# kugarem_nosilk_fix.net
KiCad netlist of a schematic drawn in EAGLE
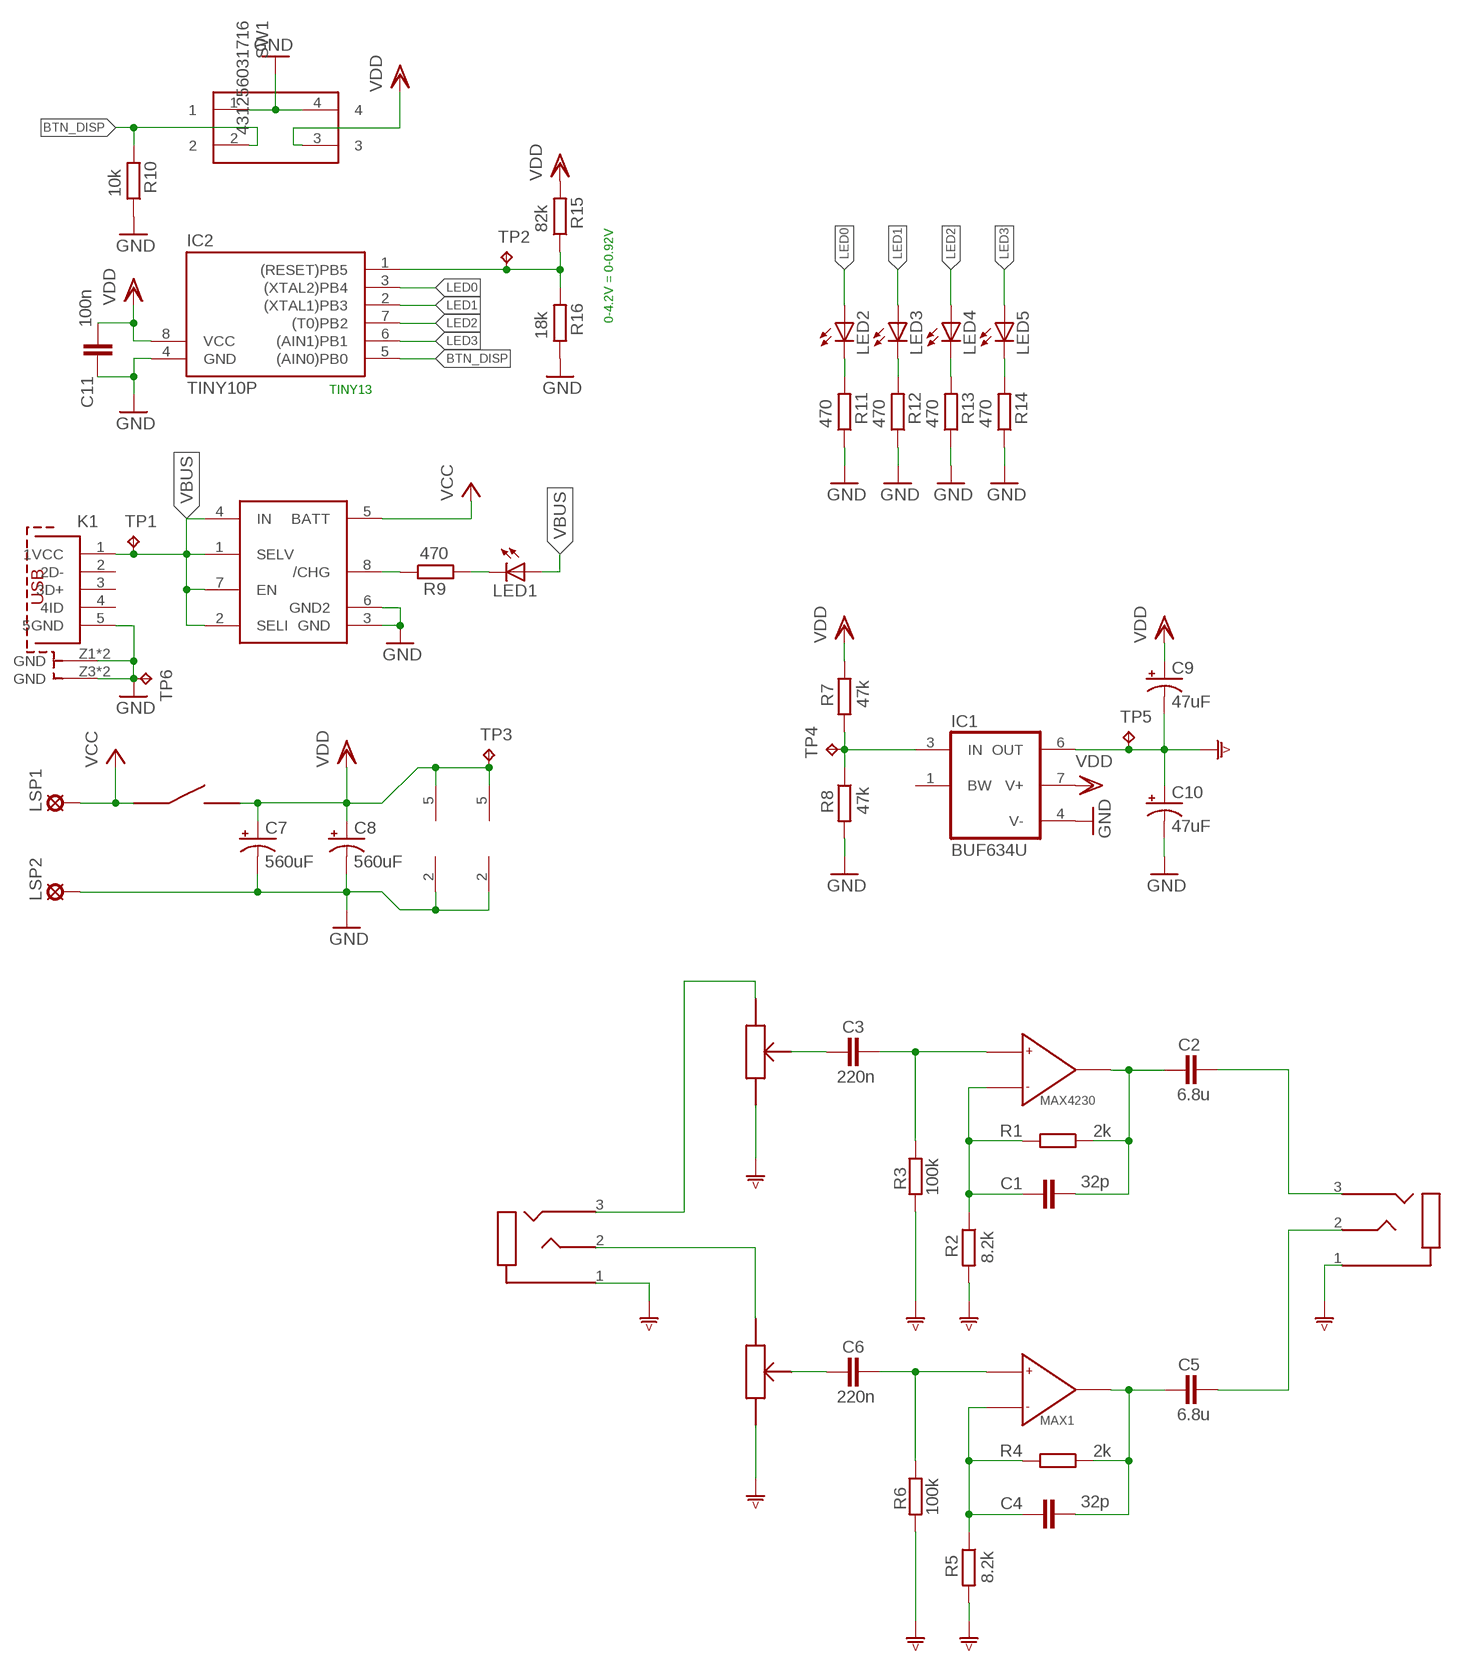
[diagram p0: schematic, sheet 1]

(export (version "E")
  (design (tool "Eeschema 10.0.6"))
  (components
    (comp (ref "C1")
      (value "32p")
      (footprint "eagle-import:C1206")
      (libsource (lib "eagle-import") (part "C-EUC1206"))
    )
    (comp (ref "C2")
      (value "6.8u")
      (footprint "eagle-import:C1206")
      (libsource (lib "eagle-import") (part "C-EUC1206"))
    )
    (comp (ref "C3")
      (value "220n")
      (footprint "eagle-import:C1206")
      (libsource (lib "eagle-import") (part "C-EUC1206"))
    )
    (comp (ref "C4")
      (value "32p")
      (footprint "eagle-import:C1206")
      (libsource (lib "eagle-import") (part "C-EUC1206"))
    )
    (comp (ref "C5")
      (value "6.8u")
      (footprint "eagle-import:C1206")
      (libsource (lib "eagle-import") (part "C-EUC1206"))
    )
    (comp (ref "C6")
      (value "220n")
      (footprint "eagle-import:C1206")
      (libsource (lib "eagle-import") (part "C-EUC1206"))
    )
    (comp (ref "C7")
      (value "560uF")
      (footprint "eagle-import:PANASONIC_G")
      (libsource (lib "eagle-import") (part "560UF-PANASONIC_G-25V-20%"))
    )
    (comp (ref "C8")
      (value "560uF")
      (footprint "eagle-import:PANASONIC_G")
      (libsource (lib "eagle-import") (part "560UF-PANASONIC_G-25V-20%"))
    )
    (comp (ref "C9")
      (value "47uF")
      (footprint "eagle-import:PANASONIC_D")
      (libsource (lib "eagle-import") (part "47UF-POLAR-PANASONIC_D-35V-20%"))
    )
    (comp (ref "C10")
      (value "47uF")
      (footprint "eagle-import:PANASONIC_D")
      (libsource (lib "eagle-import") (part "47UF-POLAR-PANASONIC_D-35V-20%"))
    )
    (comp (ref "C11")
      (value "100n")
      (footprint "eagle-import:C1206")
      (libsource (lib "eagle-import") (part "C-EUC1206"))
    )
    (comp (ref "IC1")
      (value "BUF634U")
      (footprint "eagle-import:SO08")
      (fields (field (name "MF") "TEXAS INSTRUMENTS"))
      (libsource (lib "eagle-import") (part "BUF634U"))
    )
    (comp (ref "IC2")
      (value "TINY10P")
      (footprint "eagle-import:DIL08")
      (libsource (lib "eagle-import") (part "TINY10P"))
    )
    (comp (ref "K1")
      (value "629105150521")
      (footprint "eagle-import:629105150521")
      (libsource (lib "eagle-import") (part "629105150521"))
    )
    (comp (ref "LED1")
      (value "LEDCHIPLED_1206")
      (footprint "eagle-import:CHIPLED_1206")
      (libsource (lib "eagle-import") (part "LEDCHIPLED_1206"))
    )
    (comp (ref "LED2")
      (value "LEDCHIPLED_1206")
      (footprint "eagle-import:CHIPLED_1206")
      (libsource (lib "eagle-import") (part "LEDCHIPLED_1206"))
    )
    (comp (ref "LED3")
      (value "LEDCHIPLED_1206")
      (footprint "eagle-import:CHIPLED_1206")
      (libsource (lib "eagle-import") (part "LEDCHIPLED_1206"))
    )
    (comp (ref "LED4")
      (value "LEDCHIPLED_1206")
      (footprint "eagle-import:CHIPLED_1206")
      (libsource (lib "eagle-import") (part "LEDCHIPLED_1206"))
    )
    (comp (ref "LED5")
      (value "LEDCHIPLED_1206")
      (footprint "eagle-import:CHIPLED_1206")
      (libsource (lib "eagle-import") (part "LEDCHIPLED_1206"))
    )
    (comp (ref "LSP1")
      (value "LSP10")
      (footprint "eagle-import:LSP10")
      (libsource (lib "eagle-import") (part "LSP10"))
    )
    (comp (ref "LSP2")
      (value "LSP10")
      (footprint "eagle-import:LSP10")
      (libsource (lib "eagle-import") (part "LSP10"))
    )
    (comp (ref "MAX1")
      (value "MAX4230")
      (footprint "eagle-import:SOT23-5L")
      (libsource (lib "eagle-import") (part "MAX4230"))
    )
    (comp (ref "MAX4230")
      (value "MAX4230")
      (footprint "eagle-import:SOT23-5L")
      (libsource (lib "eagle-import") (part "MAX4230"))
    )
    (comp (ref "R1")
      (value "2k")
      (footprint "eagle-import:R1206")
      (libsource (lib "eagle-import") (part "R-EU_R1206"))
    )
    (comp (ref "R2")
      (value "8.2k")
      (footprint "eagle-import:R1206")
      (libsource (lib "eagle-import") (part "R-EU_R1206"))
    )
    (comp (ref "R3")
      (value "100k")
      (footprint "eagle-import:R1206")
      (libsource (lib "eagle-import") (part "R-EU_R1206"))
    )
    (comp (ref "R4")
      (value "2k")
      (footprint "eagle-import:R1206")
      (libsource (lib "eagle-import") (part "R-EU_R1206"))
    )
    (comp (ref "R5")
      (value "8.2k")
      (footprint "eagle-import:R1206")
      (libsource (lib "eagle-import") (part "R-EU_R1206"))
    )
    (comp (ref "R6")
      (value "100k")
      (footprint "eagle-import:R1206")
      (libsource (lib "eagle-import") (part "R-EU_R1206"))
    )
    (comp (ref "R7")
      (value "47k")
      (footprint "eagle-import:R1206")
      (libsource (lib "eagle-import") (part "R-EU_R1206"))
    )
    (comp (ref "R8")
      (value "47k")
      (footprint "eagle-import:R1206")
      (libsource (lib "eagle-import") (part "R-EU_R1206"))
    )
    (comp (ref "R9")
      (value "470")
      (footprint "eagle-import:R1206")
      (libsource (lib "eagle-import") (part "R-EU_R1206"))
    )
    (comp (ref "R10")
      (value "10k")
      (footprint "eagle-import:R1206")
      (libsource (lib "eagle-import") (part "R-EU_R1206"))
    )
    (comp (ref "R11")
      (value "470")
      (footprint "eagle-import:R1206")
      (libsource (lib "eagle-import") (part "R-EU_R1206"))
    )
    (comp (ref "R12")
      (value "470")
      (footprint "eagle-import:R1206")
      (libsource (lib "eagle-import") (part "R-EU_R1206"))
    )
    (comp (ref "R13")
      (value "470")
      (footprint "eagle-import:R1206")
      (libsource (lib "eagle-import") (part "R-EU_R1206"))
    )
    (comp (ref "R14")
      (value "470")
      (footprint "eagle-import:R1206")
      (libsource (lib "eagle-import") (part "R-EU_R1206"))
    )
    (comp (ref "R15")
      (value "82k")
      (footprint "eagle-import:R1206")
      (libsource (lib "eagle-import") (part "R-EU_R1206"))
    )
    (comp (ref "R16")
      (value "18k")
      (footprint "eagle-import:R1206")
      (libsource (lib "eagle-import") (part "R-EU_R1206"))
    )
    (comp (ref "SW1")
      (value "431256031716")
      (footprint "eagle-import:431256031716")
      (libsource (lib "eagle-import") (part "431256031716"))
    )
    (comp (ref "TP1")
      (value "TPTP10SQ")
      (footprint "eagle-import:TP10SQ")
      (libsource (lib "eagle-import") (part "TPTP10SQ"))
    )
    (comp (ref "TP2")
      (value "TPTP10SQ")
      (footprint "eagle-import:TP10SQ")
      (libsource (lib "eagle-import") (part "TPTP10SQ"))
    )
    (comp (ref "TP3")
      (value "TPTP10SQ")
      (footprint "eagle-import:TP10SQ")
      (libsource (lib "eagle-import") (part "TPTP10SQ"))
    )
    (comp (ref "TP4")
      (value "TPTP10SQ")
      (footprint "eagle-import:TP10SQ")
      (libsource (lib "eagle-import") (part "TPTP10SQ"))
    )
    (comp (ref "TP5")
      (value "TPTP10SQ")
      (footprint "eagle-import:TP10SQ")
      (libsource (lib "eagle-import") (part "TPTP10SQ"))
    )
    (comp (ref "TP6")
      (value "TPTP10SQ")
      (footprint "eagle-import:TP10SQ")
      (libsource (lib "eagle-import") (part "TPTP10SQ"))
    )
    (comp (ref "U$1")
      (value "100k")
      (footprint "eagle-import:PTR902")
      (libsource (lib "eagle-import") (part "PTR90"))
    )
    (comp (ref "U$2")
      (value "SJ1-3515-SMT-TR")
      (footprint "eagle-import:STX-35332-3N-TR")
      (libsource (lib "eagle-import") (part "SJ1-3515-SMT-TR"))
    )
    (comp (ref "U$3")
      (value "SJ1-3515-SMT-TR")
      (footprint "eagle-import:STX-35332-3N-TR")
      (libsource (lib "eagle-import") (part "SJ1-3515-SMT-TR"))
    )
    (comp (ref "U$4")
      (value "MAX1811SO8")
      (footprint "eagle-import:SO08")
      (libsource (lib "eagle-import") (part "MAX1811SO8"))
    )
  )
  (nets
    (net (code "1") (name "BTN_DISP") (class "Default")
      (node (ref "IC2") (pin "5") (pinfunction "(AIN0)PB0_5") (pintype "bidirectional"))
      (node (ref "R10") (pin "2") (pinfunction "2_2") (pintype "passive"))
      (node (ref "SW1") (pin "2") (pinfunction "2_2") (pintype "bidirectional"))
    )
    (net (code "2") (name "GND") (class "Default")
      (node (ref "C10") (pin "-") (pinfunction "-_-") (pintype "passive"))
      (node (ref "C11") (pin "1") (pinfunction "1_1") (pintype "passive"))
      (node (ref "C7") (pin "-") (pinfunction "-_-") (pintype "passive"))
      (node (ref "C8") (pin "-") (pinfunction "-_-") (pintype "passive"))
      (node (ref "IC1") (pin "4") (pinfunction "V-_4") (pintype "power_in"))
      (node (ref "IC2") (pin "4") (pinfunction "GND_4") (pintype "power_in"))
      (node (ref "K1") (pin "5") (pinfunction "5GND_5") (pintype "passive"))
      (node (ref "K1") (pin "Z1") (pinfunction "GND_Z1") (pintype "bidirectional"))
      (node (ref "K1") (pin "Z2") (pinfunction "GND_Z2") (pintype "bidirectional"))
      (node (ref "K1") (pin "Z3") (pinfunction "GND_Z3") (pintype "bidirectional"))
      (node (ref "K1") (pin "Z4") (pinfunction "GND_Z4") (pintype "bidirectional"))
      (node (ref "LSP2") (pin "MP") (pinfunction "MP_MP") (pintype "passive"))
      (node (ref "MAX1") (pin "2") (pinfunction "N_2") (pintype "bidirectional"))
      (node (ref "MAX4230") (pin "2") (pinfunction "N_2") (pintype "bidirectional"))
      (node (ref "R10") (pin "1") (pinfunction "1_1") (pintype "passive"))
      (node (ref "R11") (pin "1") (pinfunction "1_1") (pintype "passive"))
      (node (ref "R12") (pin "1") (pinfunction "1_1") (pintype "passive"))
      (node (ref "R13") (pin "1") (pinfunction "1_1") (pintype "passive"))
      (node (ref "R14") (pin "1") (pinfunction "1_1") (pintype "passive"))
      (node (ref "R16") (pin "1") (pinfunction "1_1") (pintype "passive"))
      (node (ref "R8") (pin "2") (pinfunction "2_2") (pintype "passive"))
      (node (ref "SW1") (pin "1") (pinfunction "1_1") (pintype "bidirectional"))
      (node (ref "SW1") (pin "4") (pinfunction "4_4") (pintype "bidirectional"))
      (node (ref "TP6") (pin "TP") (pinfunction "TP_TP") (pintype "input"))
      (node (ref "U$4") (pin "3") (pinfunction "GND_3") (pintype "bidirectional"))
      (node (ref "U$4") (pin "6") (pinfunction "GND2_6") (pintype "bidirectional"))
    )
    (net (code "3") (name "LED0") (class "Default")
      (node (ref "IC2") (pin "3") (pinfunction "(XTAL2)PB4_3") (pintype "bidirectional"))
      (node (ref "LED2") (pin "A") (pinfunction "A_A") (pintype "passive"))
    )
    (net (code "4") (name "LED1") (class "Default")
      (node (ref "IC2") (pin "2") (pinfunction "(XTAL1)PB3_2") (pintype "bidirectional"))
      (node (ref "LED3") (pin "A") (pinfunction "A_A") (pintype "passive"))
    )
    (net (code "5") (name "LED2") (class "Default")
      (node (ref "IC2") (pin "7") (pinfunction "(T0)PB2_7") (pintype "bidirectional"))
      (node (ref "LED4") (pin "A") (pinfunction "A_A") (pintype "passive"))
    )
    (net (code "6") (name "LED3") (class "Default")
      (node (ref "IC2") (pin "6") (pinfunction "(AIN1)PB1_6") (pintype "bidirectional"))
      (node (ref "LED5") (pin "A") (pinfunction "A_A") (pintype "passive"))
    )
    (net (code "7") (name "Net-(IC1-IN)") (class "Default")
      (node (ref "IC1") (pin "3") (pinfunction "IN_3") (pintype "input"))
      (node (ref "R7") (pin "2") (pinfunction "2_2") (pintype "passive"))
      (node (ref "R8") (pin "1") (pinfunction "1_1") (pintype "passive"))
      (node (ref "TP4") (pin "TP") (pinfunction "TP_TP") (pintype "input"))
    )
    (net (code "8") (name "Net-(IC2-(RESET)PB5)") (class "Default")
      (node (ref "IC2") (pin "1") (pinfunction "(RESET)PB5_1") (pintype "bidirectional"))
      (node (ref "R15") (pin "1") (pinfunction "1_1") (pintype "passive"))
      (node (ref "R16") (pin "2") (pinfunction "2_2") (pintype "passive"))
      (node (ref "TP2") (pin "TP") (pinfunction "TP_TP") (pintype "input"))
    )
    (net (code "9") (name "Net-(LED1-PadC)") (class "Default")
      (node (ref "LED1") (pin "C") (pinfunction "C_C") (pintype "passive"))
      (node (ref "R9") (pin "2") (pinfunction "2_2") (pintype "passive"))
    )
    (net (code "10") (name "Net-(LED2-PadC)") (class "Default")
      (node (ref "LED2") (pin "C") (pinfunction "C_C") (pintype "passive"))
      (node (ref "R11") (pin "2") (pinfunction "2_2") (pintype "passive"))
    )
    (net (code "11") (name "Net-(LED3-PadC)") (class "Default")
      (node (ref "LED3") (pin "C") (pinfunction "C_C") (pintype "passive"))
      (node (ref "R12") (pin "2") (pinfunction "2_2") (pintype "passive"))
    )
    (net (code "12") (name "Net-(LED4-PadC)") (class "Default")
      (node (ref "LED4") (pin "C") (pinfunction "C_C") (pintype "passive"))
      (node (ref "R13") (pin "2") (pinfunction "2_2") (pintype "passive"))
    )
    (net (code "13") (name "Net-(LED5-PadC)") (class "Default")
      (node (ref "LED5") (pin "C") (pinfunction "C_C") (pintype "passive"))
      (node (ref "R14") (pin "2") (pinfunction "2_2") (pintype "passive"))
    )
    (net (code "14") (name "Net-(MAX1A-IN+)") (class "Default")
      (node (ref "C6") (pin "2") (pinfunction "2_2") (pintype "passive"))
      (node (ref "MAX1") (pin "1") (pinfunction "IN+_1") (pintype "bidirectional"))
      (node (ref "R6") (pin "1") (pinfunction "1_1") (pintype "passive"))
    )
    (net (code "15") (name "Net-(MAX1A-IN-)") (class "Default")
      (node (ref "C4") (pin "1") (pinfunction "1_1") (pintype "passive"))
      (node (ref "MAX1") (pin "3") (pinfunction "IN-_3") (pintype "bidirectional"))
      (node (ref "R4") (pin "2") (pinfunction "2_2") (pintype "passive"))
      (node (ref "R5") (pin "1") (pinfunction "1_1") (pintype "passive"))
    )
    (net (code "16") (name "Net-(MAX1A-OUT)") (class "Default")
      (node (ref "C4") (pin "2") (pinfunction "2_2") (pintype "passive"))
      (node (ref "C5") (pin "1") (pinfunction "1_1") (pintype "passive"))
      (node (ref "MAX1") (pin "4") (pinfunction "OUT_4") (pintype "bidirectional"))
      (node (ref "R4") (pin "1") (pinfunction "1_1") (pintype "passive"))
    )
    (net (code "17") (name "Net-(MAX4230A-IN+)") (class "Default")
      (node (ref "C3") (pin "2") (pinfunction "2_2") (pintype "passive"))
      (node (ref "MAX4230") (pin "1") (pinfunction "IN+_1") (pintype "bidirectional"))
      (node (ref "R3") (pin "1") (pinfunction "1_1") (pintype "passive"))
    )
    (net (code "18") (name "Net-(MAX4230A-IN-)") (class "Default")
      (node (ref "C1") (pin "1") (pinfunction "1_1") (pintype "passive"))
      (node (ref "MAX4230") (pin "3") (pinfunction "IN-_3") (pintype "bidirectional"))
      (node (ref "R1") (pin "2") (pinfunction "2_2") (pintype "passive"))
      (node (ref "R2") (pin "1") (pinfunction "1_1") (pintype "passive"))
    )
    (net (code "19") (name "Net-(MAX4230A-OUT)") (class "Default")
      (node (ref "C1") (pin "2") (pinfunction "2_2") (pintype "passive"))
      (node (ref "C2") (pin "1") (pinfunction "1_1") (pintype "passive"))
      (node (ref "MAX4230") (pin "4") (pinfunction "OUT_4") (pintype "bidirectional"))
      (node (ref "R1") (pin "1") (pinfunction "1_1") (pintype "passive"))
    )
    (net (code "20") (name "Net-(U$1A-11)") (class "Default")
      (node (ref "U$1") (pin "R11") (pinfunction "11_R11") (pintype "bidirectional"))
      (node (ref "U$2") (pin "2") (pinfunction "TIP_2") (pintype "bidirectional"))
    )
    (net (code "21") (name "Net-(U$1A-12)") (class "Default")
      (node (ref "C6") (pin "1") (pinfunction "1_1") (pintype "passive"))
      (node (ref "U$1") (pin "R12") (pinfunction "12_R12") (pintype "bidirectional"))
    )
    (net (code "22") (name "Net-(U$1B-11)") (class "Default")
      (node (ref "U$1") (pin "R21") (pinfunction "11_R21") (pintype "bidirectional"))
      (node (ref "U$2") (pin "3") (pinfunction "RING_3") (pintype "bidirectional"))
    )
    (net (code "23") (name "Net-(U$1B-12)") (class "Default")
      (node (ref "C3") (pin "1") (pinfunction "1_1") (pintype "passive"))
      (node (ref "U$1") (pin "R22") (pinfunction "12_R22") (pintype "bidirectional"))
    )
    (net (code "24") (name "Net-(U$3-RING)") (class "Default")
      (node (ref "C2") (pin "2") (pinfunction "2_2") (pintype "passive"))
      (node (ref "U$3") (pin "3") (pinfunction "RING_3") (pintype "bidirectional"))
    )
    (net (code "25") (name "Net-(U$3-TIP)") (class "Default")
      (node (ref "C5") (pin "2") (pinfunction "2_2") (pintype "passive"))
      (node (ref "U$3") (pin "2") (pinfunction "TIP_2") (pintype "bidirectional"))
    )
    (net (code "26") (name "Net-(U$4-{slash}CHG)") (class "Default")
      (node (ref "R9") (pin "1") (pinfunction "1_1") (pintype "passive"))
      (node (ref "U$4") (pin "8") (pinfunction "/CHG_8") (pintype "bidirectional"))
    )
    (net (code "27") (name "VBUS") (class "Default")
      (node (ref "K1") (pin "1") (pinfunction "1VCC_1") (pintype "passive"))
      (node (ref "LED1") (pin "A") (pinfunction "A_A") (pintype "passive"))
      (node (ref "TP1") (pin "TP") (pinfunction "TP_TP") (pintype "input"))
      (node (ref "U$4") (pin "1") (pinfunction "SELV_1") (pintype "bidirectional"))
      (node (ref "U$4") (pin "2") (pinfunction "SELI_2") (pintype "bidirectional"))
      (node (ref "U$4") (pin "4") (pinfunction "IN_4") (pintype "bidirectional"))
      (node (ref "U$4") (pin "7") (pinfunction "EN_7") (pintype "bidirectional"))
    )
    (net (code "28") (name "VCC") (class "Default")
      (node (ref "LSP1") (pin "MP") (pinfunction "MP_MP") (pintype "passive"))
      (node (ref "U$1") (pin "SW1") (pinfunction "11_SW1") (pintype "bidirectional"))
      (node (ref "U$4") (pin "5") (pinfunction "BATT_5") (pintype "bidirectional"))
    )
    (net (code "29") (name "VDD") (class "Default")
      (node (ref "C11") (pin "2") (pinfunction "2_2") (pintype "passive"))
      (node (ref "C7") (pin "+") (pinfunction "+_+") (pintype "passive"))
      (node (ref "C8") (pin "+") (pinfunction "+_+") (pintype "passive"))
      (node (ref "C9") (pin "+") (pinfunction "+_+") (pintype "passive"))
      (node (ref "IC1") (pin "7") (pinfunction "V+_7") (pintype "power_in"))
      (node (ref "IC2") (pin "8") (pinfunction "VCC_8") (pintype "power_in"))
      (node (ref "MAX1") (pin "5") (pinfunction "P_5") (pintype "bidirectional"))
      (node (ref "MAX4230") (pin "5") (pinfunction "P_5") (pintype "bidirectional"))
      (node (ref "R15") (pin "2") (pinfunction "2_2") (pintype "passive"))
      (node (ref "R7") (pin "1") (pinfunction "1_1") (pintype "passive"))
      (node (ref "SW1") (pin "3") (pinfunction "3_3") (pintype "bidirectional"))
      (node (ref "TP3") (pin "TP") (pinfunction "TP_TP") (pintype "input"))
      (node (ref "U$1") (pin "SW2") (pinfunction "12_SW2") (pintype "bidirectional"))
    )
    (net (code "30") (name "VGND") (class "Default")
      (node (ref "C10") (pin "+") (pinfunction "+_+") (pintype "passive"))
      (node (ref "C9") (pin "-") (pinfunction "-_-") (pintype "passive"))
      (node (ref "IC1") (pin "6") (pinfunction "OUT_6") (pintype "output"))
      (node (ref "R2") (pin "2") (pinfunction "2_2") (pintype "passive"))
      (node (ref "R3") (pin "2") (pinfunction "2_2") (pintype "passive"))
      (node (ref "R5") (pin "2") (pinfunction "2_2") (pintype "passive"))
      (node (ref "R6") (pin "2") (pinfunction "2_2") (pintype "passive"))
      (node (ref "TP5") (pin "TP") (pinfunction "TP_TP") (pintype "input"))
      (node (ref "U$1") (pin "R13") (pinfunction "13_R13") (pintype "bidirectional"))
      (node (ref "U$1") (pin "R23") (pinfunction "13_R23") (pintype "bidirectional"))
      (node (ref "U$2") (pin "1") (pinfunction "SLEEVE_1") (pintype "bidirectional"))
      (node (ref "U$3") (pin "1") (pinfunction "SLEEVE_1") (pintype "bidirectional"))
    )
    (net (code "31") (name "unconnected-(IC1-BW-Pad1)") (class "Default")
      (node (ref "IC1") (pin "1") (pinfunction "BW_1") (pintype "passive"))
    )
    (net (code "32") (name "unconnected-(K1-2D--Pad2)") (class "Default")
      (node (ref "K1") (pin "2") (pinfunction "2D-_2") (pintype "passive"))
    )
    (net (code "33") (name "unconnected-(K1-3D+-Pad3)") (class "Default")
      (node (ref "K1") (pin "3") (pinfunction "3D+_3") (pintype "passive"))
    )
    (net (code "34") (name "unconnected-(K1-4ID-Pad4)") (class "Default")
      (node (ref "K1") (pin "4") (pinfunction "4ID_4") (pintype "passive"))
    )
  )
)
